# cubex_motherboard.net
KiCad netlist of a schematic drawn in EAGLE
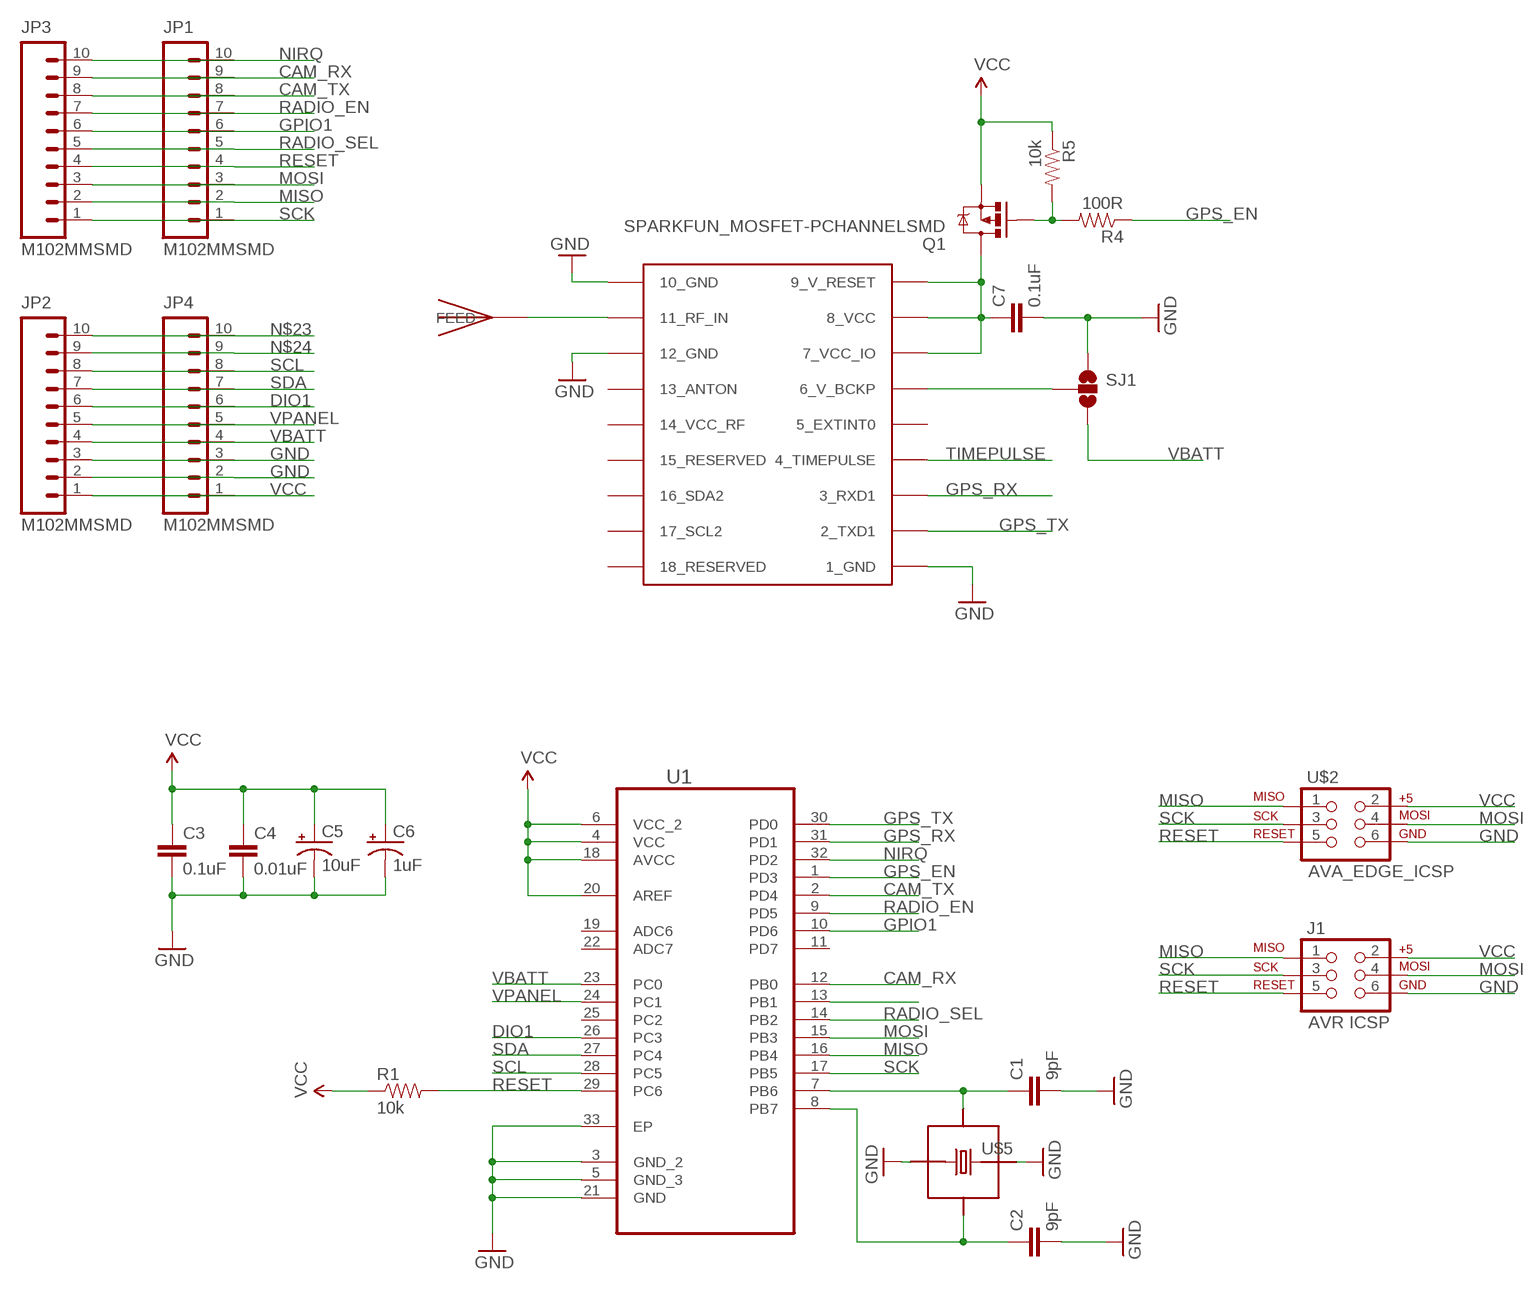
[diagram p0: schematic, sheet 1]

(export (version "E")
  (design (tool "Eeschema 10.0.6"))
  (components
    (comp (ref "C1")
      (value "9pF")
      (footprint "eagle-import:0805")
      (libsource (lib "eagle-import") (part "CAP0805"))
    )
    (comp (ref "C2")
      (value "9pF")
      (footprint "eagle-import:0805")
      (libsource (lib "eagle-import") (part "CAP0805"))
    )
    (comp (ref "C3")
      (value "0.1uF")
      (footprint "eagle-import:0805")
      (libsource (lib "eagle-import") (part "CAP0805"))
    )
    (comp (ref "C4")
      (value "0.01uF")
      (footprint "eagle-import:0805")
      (libsource (lib "eagle-import") (part "CAP0805"))
    )
    (comp (ref "C5")
      (value "10uF")
      (footprint "eagle-import:EIA3216")
      (libsource (lib "eagle-import") (part "CAP_POL1206"))
    )
    (comp (ref "C6")
      (value "1uF")
      (footprint "eagle-import:EIA3216")
      (libsource (lib "eagle-import") (part "CAP_POL1206"))
    )
    (comp (ref "C7")
      (value "0.1uF")
      (footprint "eagle-import:SPARKFUN_0805")
      (libsource (lib "eagle-import") (part "SPARKFUN_CAP0805"))
    )
    (comp (ref "J1")
      (value "AVR ICSP")
      (footprint "eagle-import:SPARKFUN_2X3-NS")
      (libsource (lib "eagle-import") (part "SPARKFUN_AVR_SPI_PRG_6NS"))
    )
    (comp (ref "JP1")
      (value "M102MMSMD")
      (footprint "eagle-import:1X10-2MM-SMD")
      (libsource (lib "eagle-import") (part "M102MMSMD"))
    )
    (comp (ref "JP2")
      (value "M102MMSMD")
      (footprint "eagle-import:1X10-2MM-SMD")
      (libsource (lib "eagle-import") (part "M102MMSMD"))
    )
    (comp (ref "JP3")
      (value "M102MMSMD")
      (footprint "eagle-import:1X10-2MM-SMD")
      (libsource (lib "eagle-import") (part "M102MMSMD"))
    )
    (comp (ref "JP4")
      (value "M102MMSMD")
      (footprint "eagle-import:1X10-2MM-SMD")
      (libsource (lib "eagle-import") (part "M102MMSMD"))
    )
    (comp (ref "Q1")
      (value "SPARKFUN_MOSFET-PCHANNELSMD")
      (footprint "eagle-import:SPARKFUN_SOT23-3")
      (libsource (lib "eagle-import") (part "SPARKFUN_MOSFET-PCHANNELSMD"))
    )
    (comp (ref "R1")
      (value "10k")
      (footprint "eagle-import:0805")
      (libsource (lib "eagle-import") (part "RESISTOR0805-RES"))
    )
    (comp (ref "R4")
      (value "100R")
      (footprint "eagle-import:SPARKFUN_0805")
      (libsource (lib "eagle-import") (part "SPARKFUN_RESISTOR0805-RES"))
    )
    (comp (ref "R5")
      (value "10k")
      (footprint "eagle-import:SPARKFUN_0805")
      (libsource (lib "eagle-import") (part "SPARKFUN_RESISTOR0805-RES"))
    )
    (comp (ref "SJ1")
      (value "SPARKFUN_SOLDERJUMPER_2WAYT")
      (footprint "eagle-import:SPARKFUN_SJ_2")
      (libsource (lib "eagle-import") (part "SPARKFUN_SOLDERJUMPER_2WAYT"))
    )
    (comp (ref "U$2")
      (value "AVA_EDGE_ICSP")
      (footprint "eagle-import:AVA_EDGE_MOUNTED_ICSP")
      (libsource (lib "eagle-import") (part "AVA_EDGE_ICSP"))
    )
    (comp (ref "U$3")
      (value "AVA_JTI_ANTENNA-1575AT43A40")
      (footprint "eagle-import:AVA_JTI_ANTENNA-1575AT43A40")
      (libsource (lib "eagle-import") (part "AVA_JTI_ANTENNA-1575AT43A40"))
    )
    (comp (ref "U$4")
      (value "AVA_UBLOX_MAX-6")
      (footprint "eagle-import:AVA_UBLOX_MAX-6")
      (libsource (lib "eagle-import") (part "AVA_UBLOX_MAX-6"))
    )
    (comp (ref "U$5")
      (value "AVA_EPSON_FA-20H_CRYSTAL")
      (footprint "eagle-import:AVA_EPSON-FA-20H-CRYSTAL")
      (libsource (lib "eagle-import") (part "AVA_EPSON_FA-20H_CRYSTAL"))
    )
    (comp (ref "U1")
      (value "AVA_ATMEGA328P-MU")
      (footprint "eagle-import:AVA_QFN50P500X500X100-33N")
      (fields (field (name "MPN") "ATMEGA328P-MU"))
      (libsource (lib "eagle-import") (part "AVA_ATMEGA328P-MU"))
    )
  )
  (nets
    (net (code "1") (name "/CAM_RX") (class "Default")
      (node (ref "JP1") (pin "9") (pinfunction "9_9") (pintype "passive"))
      (node (ref "JP3") (pin "9") (pinfunction "9_9") (pintype "passive"))
      (node (ref "U1") (pin "12") (pinfunction "PB0_12") (pintype "bidirectional"))
    )
    (net (code "2") (name "/CAM_TX") (class "Default")
      (node (ref "JP1") (pin "8") (pinfunction "8_8") (pintype "passive"))
      (node (ref "JP3") (pin "8") (pinfunction "8_8") (pintype "passive"))
      (node (ref "U1") (pin "2") (pinfunction "PD4_2") (pintype "bidirectional"))
    )
    (net (code "3") (name "/DIO1") (class "Default")
      (node (ref "JP2") (pin "6") (pinfunction "6_6") (pintype "passive"))
      (node (ref "JP4") (pin "6") (pinfunction "6_6") (pintype "passive"))
      (node (ref "U1") (pin "26") (pinfunction "PC3_26") (pintype "bidirectional"))
    )
    (net (code "4") (name "/GPIO1") (class "Default")
      (node (ref "JP1") (pin "6") (pinfunction "6_6") (pintype "passive"))
      (node (ref "JP3") (pin "6") (pinfunction "6_6") (pintype "passive"))
      (node (ref "U1") (pin "10") (pinfunction "PD6_10") (pintype "bidirectional"))
    )
    (net (code "5") (name "/GPS_EN") (class "Default")
      (node (ref "R4") (pin "1") (pinfunction "1_1") (pintype "passive"))
      (node (ref "U1") (pin "1") (pinfunction "PD3_1") (pintype "bidirectional"))
    )
    (net (code "6") (name "/GPS_RX") (class "Default")
      (node (ref "U$4") (pin "3_RXD1") (pinfunction "3_RXD1_3_RXD1") (pintype "bidirectional"))
      (node (ref "U1") (pin "31") (pinfunction "PD1_31") (pintype "bidirectional"))
    )
    (net (code "7") (name "/GPS_TX") (class "Default")
      (node (ref "U$4") (pin "2_TXD1") (pinfunction "2_TXD1_2_TXD1") (pintype "bidirectional"))
      (node (ref "U1") (pin "30") (pinfunction "PD0_30") (pintype "bidirectional"))
    )
    (net (code "8") (name "/MISO") (class "Default")
      (node (ref "J1") (pin "1") (pinfunction "1_1") (pintype "passive"))
      (node (ref "JP1") (pin "2") (pinfunction "2_2") (pintype "passive"))
      (node (ref "JP3") (pin "2") (pinfunction "2_2") (pintype "passive"))
      (node (ref "U$2") (pin "1") (pinfunction "1_1") (pintype "passive"))
      (node (ref "U1") (pin "16") (pinfunction "PB4_16") (pintype "bidirectional"))
    )
    (net (code "9") (name "/MOSI") (class "Default")
      (node (ref "J1") (pin "4") (pinfunction "4_4") (pintype "passive"))
      (node (ref "JP1") (pin "3") (pinfunction "3_3") (pintype "passive"))
      (node (ref "JP3") (pin "3") (pinfunction "3_3") (pintype "passive"))
      (node (ref "U$2") (pin "4") (pinfunction "4_4") (pintype "passive"))
      (node (ref "U1") (pin "15") (pinfunction "PB3_15") (pintype "bidirectional"))
    )
    (net (code "10") (name "/N$23") (class "Default")
      (node (ref "JP2") (pin "10") (pinfunction "10_10") (pintype "passive"))
      (node (ref "JP4") (pin "10") (pinfunction "10_10") (pintype "passive"))
    )
    (net (code "11") (name "/N$24") (class "Default")
      (node (ref "JP2") (pin "9") (pinfunction "9_9") (pintype "passive"))
      (node (ref "JP4") (pin "9") (pinfunction "9_9") (pintype "passive"))
    )
    (net (code "12") (name "/NIRQ") (class "Default")
      (node (ref "JP1") (pin "10") (pinfunction "10_10") (pintype "passive"))
      (node (ref "JP3") (pin "10") (pinfunction "10_10") (pintype "passive"))
      (node (ref "U1") (pin "32") (pinfunction "PD2_32") (pintype "bidirectional"))
    )
    (net (code "13") (name "/RADIO_EN") (class "Default")
      (node (ref "JP1") (pin "7") (pinfunction "7_7") (pintype "passive"))
      (node (ref "JP3") (pin "7") (pinfunction "7_7") (pintype "passive"))
      (node (ref "U1") (pin "9") (pinfunction "PD5_9") (pintype "bidirectional"))
    )
    (net (code "14") (name "/RADIO_SEL") (class "Default")
      (node (ref "JP1") (pin "5") (pinfunction "5_5") (pintype "passive"))
      (node (ref "JP3") (pin "5") (pinfunction "5_5") (pintype "passive"))
      (node (ref "U1") (pin "14") (pinfunction "PB2_14") (pintype "bidirectional"))
    )
    (net (code "15") (name "/RESET") (class "Default")
      (node (ref "J1") (pin "5") (pinfunction "5_5") (pintype "passive"))
      (node (ref "JP1") (pin "4") (pinfunction "4_4") (pintype "passive"))
      (node (ref "JP3") (pin "4") (pinfunction "4_4") (pintype "passive"))
      (node (ref "R1") (pin "2") (pinfunction "2_2") (pintype "passive"))
      (node (ref "U$2") (pin "5") (pinfunction "5_5") (pintype "passive"))
      (node (ref "U1") (pin "29") (pinfunction "PC6_29") (pintype "bidirectional"))
    )
    (net (code "16") (name "/SCK") (class "Default")
      (node (ref "J1") (pin "3") (pinfunction "3_3") (pintype "passive"))
      (node (ref "JP1") (pin "1") (pinfunction "1_1") (pintype "passive"))
      (node (ref "JP3") (pin "1") (pinfunction "1_1") (pintype "passive"))
      (node (ref "U$2") (pin "3") (pinfunction "3_3") (pintype "passive"))
      (node (ref "U1") (pin "17") (pinfunction "PB5_17") (pintype "bidirectional"))
    )
    (net (code "17") (name "/SCL") (class "Default")
      (node (ref "JP2") (pin "8") (pinfunction "8_8") (pintype "passive"))
      (node (ref "JP4") (pin "8") (pinfunction "8_8") (pintype "passive"))
      (node (ref "U1") (pin "28") (pinfunction "PC5_28") (pintype "bidirectional"))
    )
    (net (code "18") (name "/SDA") (class "Default")
      (node (ref "JP2") (pin "7") (pinfunction "7_7") (pintype "passive"))
      (node (ref "JP4") (pin "7") (pinfunction "7_7") (pintype "passive"))
      (node (ref "U1") (pin "27") (pinfunction "PC4_27") (pintype "bidirectional"))
    )
    (net (code "19") (name "/TIMEPULSE") (class "Default")
      (node (ref "U$4") (pin "4_TIMEPULSE") (pinfunction "4_TIMEPULSE_4_TIMEPULSE") (pintype "bidirectional"))
    )
    (net (code "20") (name "/VBATT") (class "Default")
      (node (ref "JP2") (pin "4") (pinfunction "4_4") (pintype "passive"))
      (node (ref "JP4") (pin "4") (pinfunction "4_4") (pintype "passive"))
      (node (ref "SJ1") (pin "3") (pinfunction "3_3") (pintype "passive"))
      (node (ref "U1") (pin "23") (pinfunction "PC0_23") (pintype "bidirectional"))
    )
    (net (code "21") (name "/VPANEL") (class "Default")
      (node (ref "JP2") (pin "5") (pinfunction "5_5") (pintype "passive"))
      (node (ref "JP4") (pin "5") (pinfunction "5_5") (pintype "passive"))
      (node (ref "U1") (pin "24") (pinfunction "PC1_24") (pintype "bidirectional"))
    )
    (net (code "22") (name "GND") (class "Default")
      (node (ref "C1") (pin "2") (pinfunction "2_2") (pintype "passive"))
      (node (ref "C2") (pin "2") (pinfunction "2_2") (pintype "passive"))
      (node (ref "C3") (pin "2") (pinfunction "2_2") (pintype "passive"))
      (node (ref "C4") (pin "2") (pinfunction "2_2") (pintype "passive"))
      (node (ref "C5") (pin "C") (pinfunction "-_C") (pintype "passive"))
      (node (ref "C6") (pin "C") (pinfunction "-_C") (pintype "passive"))
      (node (ref "C7") (pin "2") (pinfunction "2_2") (pintype "passive"))
      (node (ref "J1") (pin "6") (pinfunction "6_6") (pintype "passive"))
      (node (ref "JP2") (pin "2") (pinfunction "2_2") (pintype "passive"))
      (node (ref "JP2") (pin "3") (pinfunction "3_3") (pintype "passive"))
      (node (ref "JP4") (pin "2") (pinfunction "2_2") (pintype "passive"))
      (node (ref "JP4") (pin "3") (pinfunction "3_3") (pintype "passive"))
      (node (ref "SJ1") (pin "1") (pinfunction "1_1") (pintype "passive"))
      (node (ref "U$2") (pin "6") (pinfunction "6_6") (pintype "passive"))
      (node (ref "U$4") (pin "10_GND") (pinfunction "10_GND_10_GND") (pintype "bidirectional"))
      (node (ref "U$4") (pin "12_GND") (pinfunction "12_GND_12_GND") (pintype "bidirectional"))
      (node (ref "U$4") (pin "1_GND") (pinfunction "1_GND_1_GND") (pintype "bidirectional"))
      (node (ref "U$5") (pin "1") (pinfunction "1_1") (pintype "passive"))
      (node (ref "U$5") (pin "3") (pinfunction "3_3") (pintype "passive"))
      (node (ref "U1") (pin "21") (pinfunction "GND_21") (pintype "passive"))
      (node (ref "U1") (pin "3") (pinfunction "GND_2_3") (pintype "passive"))
      (node (ref "U1") (pin "33") (pinfunction "EP_33") (pintype "passive"))
      (node (ref "U1") (pin "5") (pinfunction "GND_3_5") (pintype "passive"))
    )
    (net (code "23") (name "Net-(Q1-D)") (class "Default")
      (node (ref "C7") (pin "1") (pinfunction "1_1") (pintype "passive"))
      (node (ref "Q1") (pin "3") (pinfunction "D_3") (pintype "passive"))
      (node (ref "U$4") (pin "7_VCC_IO") (pinfunction "7_VCC_IO_7_VCC_IO") (pintype "bidirectional"))
      (node (ref "U$4") (pin "8_VCC") (pinfunction "8_VCC_8_VCC") (pintype "bidirectional"))
      (node (ref "U$4") (pin "9_V_RESET") (pinfunction "9_V_RESET_9_V_RESET") (pintype "bidirectional"))
    )
    (net (code "24") (name "Net-(Q1-G)") (class "Default")
      (node (ref "Q1") (pin "1") (pinfunction "G_1") (pintype "passive"))
      (node (ref "R4") (pin "2") (pinfunction "2_2") (pintype "passive"))
      (node (ref "R5") (pin "2") (pinfunction "2_2") (pintype "passive"))
    )
    (net (code "25") (name "Net-(SJ1-Pad2)") (class "Default")
      (node (ref "SJ1") (pin "2") (pinfunction "2_2") (pintype "passive"))
      (node (ref "U$4") (pin "6_V_BCKP") (pinfunction "6_V_BCKP_6_V_BCKP") (pintype "bidirectional"))
    )
    (net (code "26") (name "Net-(U$3-PadFEED)") (class "Default")
      (node (ref "U$3") (pin "FEED") (pinfunction "FEED_FEED") (pintype "bidirectional"))
      (node (ref "U$4") (pin "11_RF_IN") (pinfunction "11_RF_IN_11_RF_IN") (pintype "bidirectional"))
    )
    (net (code "27") (name "Net-(U1-PB6)") (class "Default")
      (node (ref "C1") (pin "1") (pinfunction "1_1") (pintype "passive"))
      (node (ref "U$5") (pin "4") (pinfunction "4_4") (pintype "passive"))
      (node (ref "U1") (pin "7") (pinfunction "PB6_7") (pintype "bidirectional"))
    )
    (net (code "28") (name "Net-(U1-PB7)") (class "Default")
      (node (ref "C2") (pin "1") (pinfunction "1_1") (pintype "passive"))
      (node (ref "U$5") (pin "2") (pinfunction "2_2") (pintype "passive"))
      (node (ref "U1") (pin "8") (pinfunction "PB7_8") (pintype "bidirectional"))
    )
    (net (code "29") (name "VCC") (class "Default")
      (node (ref "C3") (pin "1") (pinfunction "1_1") (pintype "passive"))
      (node (ref "C4") (pin "1") (pinfunction "1_1") (pintype "passive"))
      (node (ref "C5") (pin "A") (pinfunction "+_A") (pintype "passive"))
      (node (ref "C6") (pin "A") (pinfunction "+_A") (pintype "passive"))
      (node (ref "J1") (pin "2") (pinfunction "2_2") (pintype "passive"))
      (node (ref "JP2") (pin "1") (pinfunction "1_1") (pintype "passive"))
      (node (ref "JP4") (pin "1") (pinfunction "1_1") (pintype "passive"))
      (node (ref "Q1") (pin "2") (pinfunction "S_2") (pintype "passive"))
      (node (ref "R1") (pin "1") (pinfunction "1_1") (pintype "passive"))
      (node (ref "R5") (pin "1") (pinfunction "1_1") (pintype "passive"))
      (node (ref "U$2") (pin "2") (pinfunction "2_2") (pintype "passive"))
      (node (ref "U1") (pin "18") (pinfunction "AVCC_18") (pintype "power_in"))
      (node (ref "U1") (pin "20") (pinfunction "AREF_20") (pintype "input"))
      (node (ref "U1") (pin "4") (pinfunction "VCC_4") (pintype "power_in"))
      (node (ref "U1") (pin "6") (pinfunction "VCC_2_6") (pintype "power_in"))
    )
    (net (code "30") (name "unconnected-(U$4-Pad5_EXTINT0)") (class "Default")
      (node (ref "U$4") (pin "5_EXTINT0") (pinfunction "5_EXTINT0_5_EXTINT0") (pintype "bidirectional"))
    )
    (net (code "31") (name "unconnected-(U$4-Pad13_ANTON)") (class "Default")
      (node (ref "U$4") (pin "13_ANTON") (pinfunction "13_ANTON_13_ANTON") (pintype "bidirectional"))
    )
    (net (code "32") (name "unconnected-(U$4-Pad14_VCC_RF)") (class "Default")
      (node (ref "U$4") (pin "14_VCC_RF") (pinfunction "14_VCC_RF_14_VCC_RF") (pintype "bidirectional"))
    )
    (net (code "33") (name "unconnected-(U$4-Pad15_RESERVED)") (class "Default")
      (node (ref "U$4") (pin "15_RESERVED") (pinfunction "15_RESERVED_15_RESERVED") (pintype "bidirectional"))
    )
    (net (code "34") (name "unconnected-(U$4-Pad16_SDA2)") (class "Default")
      (node (ref "U$4") (pin "16_SDA2") (pinfunction "16_SDA2_16_SDA2") (pintype "bidirectional"))
    )
    (net (code "35") (name "unconnected-(U$4-Pad17_SCL2)") (class "Default")
      (node (ref "U$4") (pin "17_SCL2") (pinfunction "17_SCL2_17_SCL2") (pintype "bidirectional"))
    )
    (net (code "36") (name "unconnected-(U$4-Pad18_RESERVED)") (class "Default")
      (node (ref "U$4") (pin "18_RESERVED") (pinfunction "18_RESERVED_18_RESERVED") (pintype "bidirectional"))
    )
    (net (code "37") (name "unconnected-(U1-ADC6-Pad19)") (class "Default")
      (node (ref "U1") (pin "19") (pinfunction "ADC6_19") (pintype "input"))
    )
    (net (code "38") (name "unconnected-(U1-ADC7-Pad22)") (class "Default")
      (node (ref "U1") (pin "22") (pinfunction "ADC7_22") (pintype "input"))
    )
    (net (code "39") (name "unconnected-(U1-PB1-Pad13)") (class "Default")
      (node (ref "U1") (pin "13") (pinfunction "PB1_13") (pintype "bidirectional"))
    )
    (net (code "40") (name "unconnected-(U1-PC2-Pad25)") (class "Default")
      (node (ref "U1") (pin "25") (pinfunction "PC2_25") (pintype "bidirectional"))
    )
    (net (code "41") (name "unconnected-(U1-PD7-Pad11)") (class "Default")
      (node (ref "U1") (pin "11") (pinfunction "PD7_11") (pintype "bidirectional"))
    )
  )
)
